# flexPCB.net
KiCad netlist of a schematic drawn in Altium Designer
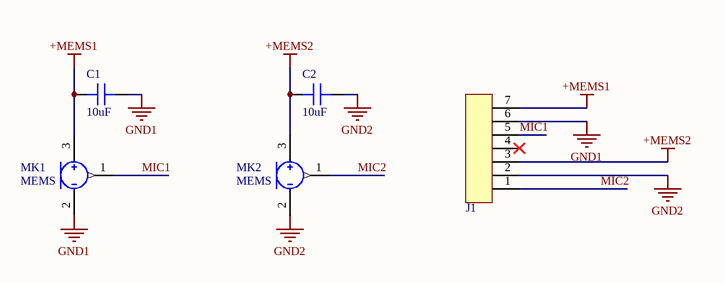
[diagram p0: flexPCB.SchDoc]

(export (version "E")
  (design (tool "Eeschema 10.0.6"))
  (components
    (comp (ref "C1")
      (value "10uF")
      (footprint "CAP 0402/1005")
      (description "CAP CER 10UF 6.3V X5R 0402")
      (fields
        (field (name "PART NUMBER") "C1005X5R0J106M050BC")
        (field (name "MANUFACTURER") "TDK Corporation")
      )
      (libsource (lib "Celestial Library Database") (part "Capacitor"))
    )
    (comp (ref "C2")
      (value "10uF")
      (footprint "CAP 0402/1005")
      (description "CAP CER 10UF 6.3V X5R 0402")
      (fields
        (field (name "PART NUMBER") "C1005X5R0J106M050BC")
        (field (name "MANUFACTURER") "TDK Corporation")
      )
      (libsource (lib "Celestial Library Database") (part "Capacitor"))
    )
    (comp (ref "J1")
      (value "FFC EDGE BOTTOM")
      (footprint "HIROSE_FH58M-7S-0.25SHW-99_BOTTOMFFC")
      (description "Bottom FFC Land Pattern for Hirose FH58M-7S-0.25SHW(99) 7-pin Top+Bottom Contact FFC Connector")
      (libsource (lib "OSP_Symbols") (part "HIROSE_FH58M-7S-0.25SHW-99_BOTTOM"))
    )
    (comp (ref "MK1")
      (value "MEMS")
      (footprint "MIC_CAGRI")
      (description "Generic 3-pin bottom mount MEMS mic, with Cagri extended footprint")
      (libsource (lib "OSP_Symbols") (part "Mems_Mic_Cagri"))
    )
    (comp (ref "MK2")
      (value "MEMS")
      (footprint "MIC_CAGRI")
      (description "Generic 3-pin bottom mount MEMS mic, with Cagri extended footprint")
      (libsource (lib "OSP_Symbols") (part "Mems_Mic_Cagri"))
    )
  )
  (nets
    (net (code "1") (name "+MEMS1") (class "Default")
      (node (ref "C1") (pin "1") (pinfunction "1_1") (pintype "passive"))
      (node (ref "J1") (pin "7") (pintype "passive"))
      (node (ref "MK1") (pin "3") (pinfunction "VDD_3") (pintype "power_in"))
    )
    (net (code "2") (name "+MEMS2") (class "Default")
      (node (ref "C2") (pin "1") (pinfunction "1_1") (pintype "passive"))
      (node (ref "J1") (pin "3") (pintype "passive"))
      (node (ref "MK2") (pin "3") (pinfunction "VDD_3") (pintype "power_in"))
    )
    (net (code "3") (name "/MIC1") (class "Default")
      (node (ref "J1") (pin "5") (pintype "passive"))
      (node (ref "MK1") (pin "1") (pintype "output"))
    )
    (net (code "4") (name "/MIC2") (class "Default")
      (node (ref "J1") (pin "1") (pintype "passive"))
      (node (ref "MK2") (pin "1") (pintype "output"))
    )
    (net (code "5") (name "GND1") (class "Default")
      (node (ref "C1") (pin "2") (pinfunction "2_2") (pintype "passive"))
      (node (ref "J1") (pin "6") (pintype "passive"))
      (node (ref "MK1") (pin "2") (pinfunction "GND_2") (pintype "power_in"))
    )
    (net (code "6") (name "GND2") (class "Default")
      (node (ref "C2") (pin "2") (pinfunction "2_2") (pintype "passive"))
      (node (ref "J1") (pin "2") (pintype "passive"))
      (node (ref "MK2") (pin "2") (pinfunction "GND_2") (pintype "power_in"))
    )
    (net (code "7") (name "unconnected-(J1-Pad4)") (class "Default")
      (node (ref "J1") (pin "4") (pintype "passive+no_connect"))
    )
  )
)
